# compute_module_Ethernet.net
KiCad netlist of a schematic drawn in Altium Designer
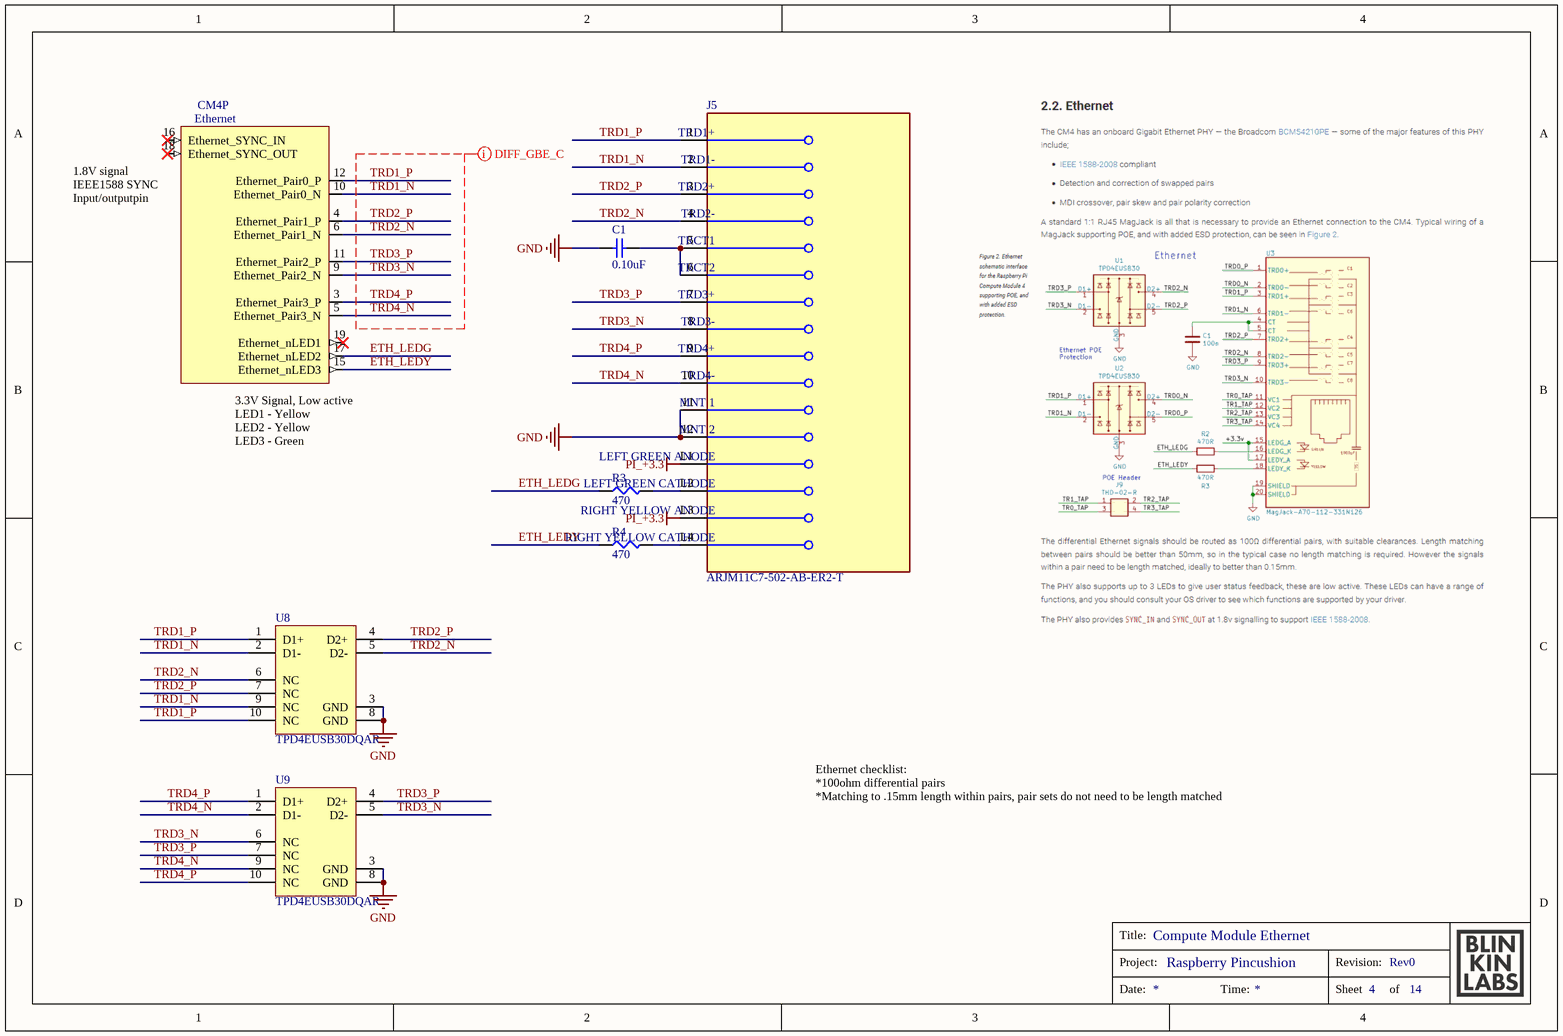
[diagram p0: compute module Ethernet.SchDoc]

(export (version "E")
  (design (tool "Eeschema 10.0.6"))
  (components
    (comp (ref "C1")
      (value "0.10uF")
      (footprint "CAPC1608X09L")
      (description "CAP CER 0.1UF 50V X7R 0603")
      (fields
        (field (name "PARTNUMBER") "GRM188R71H104KA93D")
        (field (name "DIGI-KEY PART NUMBER") "490-1519-1-ND")
      )
      (libsource (lib "cap_murata") (part "CAPACITOR"))
    )
    (comp (ref "CM4")
      (value "Raspberry Pi Compute Module 4")
      (footprint "CM4-F40C-100DS-0.4v_1.5mm_0mm")
      (description "Raspberry Pi Compute Module 4 by Amornthep Phunsin")
      (libsource (lib "CM4") (part "CM4"))
    )
    (comp (ref "J5")
      (value "ARJM11C7-502-AB-ER2-T")
      (footprint "FP-ARJM11C7-502-AB-ER2-T-MFG")
      (description "RJ45 JACK W/MAG 1X1 1000BASE-T")
      (fields
        (field (name "MANUFACTURER") "Abracon")
        (field (name "OCTOPART") "https://octopart.com/arjm11c7-502-ab-er2-t-abracon-86945316")
      )
      (libsource (lib "Altium Content Vault") (part "c9e9675df30893a1b3e4105448caa83"))
    )
    (comp (ref "R3")
      (value "470")
      (footprint "ERJ2G(0402)_L")
      (description "RES SMD 470 OHM 5% 1/10W 0402")
      (fields (field (name "PARTNUMBER") "ERJ-2GEJ471X") (field (name "DIGI-KEY PART NUMBER") "P470JCT-ND"))
      (libsource (lib "res_panasonic_erj_xls") (part "RESISTOR"))
    )
    (comp (ref "R4")
      (value "470")
      (footprint "ERJ2G(0402)_L")
      (description "RES SMD 470 OHM 5% 1/10W 0402")
      (fields (field (name "PARTNUMBER") "ERJ-2GEJ471X") (field (name "DIGI-KEY PART NUMBER") "P470JCT-ND"))
      (libsource (lib "res_panasonic_erj_xls") (part "RESISTOR"))
    )
    (comp (ref "U8")
      (value "TPD4EUSB30DQAR")
      (footprint "DQA0010A_V")
      (fields (field (name "MANUFACTURER") "Texas Instruments"))
      (libsource (lib "Altium Content Vault") (part "TI-TPD4EUSB30-SON_DQA-10"))
    )
    (comp (ref "U9")
      (value "TPD4EUSB30DQAR")
      (footprint "DQA0010A_V")
      (fields (field (name "MANUFACTURER") "Texas Instruments"))
      (libsource (lib "Altium Content Vault") (part "TI-TPD4EUSB30-SON_DQA-10"))
    )
  )
  (nets
    (net (code "1") (name "/ETH_LEDG") (class "Default")
      (node (ref "CM4") (pin "17") (pinfunction "Ethernet_nLED2_17") (pintype "output"))
      (node (ref "R3") (pin "1") (pinfunction "1_1") (pintype "passive"))
    )
    (net (code "2") (name "/ETH_LEDY") (class "Default")
      (node (ref "CM4") (pin "15") (pinfunction "Ethernet_nLED3_15") (pintype "output"))
      (node (ref "R4") (pin "1") (pinfunction "1_1") (pintype "passive"))
    )
    (net (code "3") (name "/TRD1_N") (class "Default")
      (node (ref "CM4") (pin "10") (pinfunction "Ethernet_Pair0_N_10") (pintype "passive"))
      (node (ref "J5") (pin "2") (pinfunction "TRD1-_2") (pintype "passive"))
      (node (ref "U8") (pin "2") (pinfunction "D1-_2") (pintype "passive"))
      (node (ref "U8") (pin "9") (pinfunction "NC_9") (pintype "passive"))
    )
    (net (code "4") (name "/TRD1_P") (class "Default")
      (node (ref "CM4") (pin "12") (pinfunction "Ethernet_Pair0_P_12") (pintype "passive"))
      (node (ref "J5") (pin "1") (pinfunction "TRD1+_1") (pintype "passive"))
      (node (ref "U8") (pin "1") (pinfunction "D1+_1") (pintype "passive"))
      (node (ref "U8") (pin "10") (pinfunction "NC_10") (pintype "passive"))
    )
    (net (code "5") (name "/TRD2_N") (class "Default")
      (node (ref "CM4") (pin "6") (pinfunction "Ethernet_Pair1_N_6") (pintype "passive"))
      (node (ref "J5") (pin "4") (pinfunction "TRD2-_4") (pintype "passive"))
      (node (ref "U8") (pin "5") (pinfunction "D2-_5") (pintype "passive"))
      (node (ref "U8") (pin "6") (pinfunction "NC_6") (pintype "passive"))
    )
    (net (code "6") (name "/TRD2_P") (class "Default")
      (node (ref "CM4") (pin "4") (pinfunction "Ethernet_Pair1_P_4") (pintype "passive"))
      (node (ref "J5") (pin "3") (pinfunction "TRD2+_3") (pintype "passive"))
      (node (ref "U8") (pin "4") (pinfunction "D2+_4") (pintype "passive"))
      (node (ref "U8") (pin "7") (pinfunction "NC_7") (pintype "passive"))
    )
    (net (code "7") (name "/TRD3_N") (class "Default")
      (node (ref "CM4") (pin "9") (pinfunction "Ethernet_Pair2_N_9") (pintype "passive"))
      (node (ref "J5") (pin "8") (pinfunction "TRD3-_8") (pintype "passive"))
      (node (ref "U9") (pin "5") (pinfunction "D2-_5") (pintype "passive"))
      (node (ref "U9") (pin "6") (pinfunction "NC_6") (pintype "passive"))
    )
    (net (code "8") (name "/TRD3_P") (class "Default")
      (node (ref "CM4") (pin "11") (pinfunction "Ethernet_Pair2_P_11") (pintype "passive"))
      (node (ref "J5") (pin "7") (pinfunction "TRD3+_7") (pintype "passive"))
      (node (ref "U9") (pin "4") (pinfunction "D2+_4") (pintype "passive"))
      (node (ref "U9") (pin "7") (pinfunction "NC_7") (pintype "passive"))
    )
    (net (code "9") (name "/TRD4_N") (class "Default")
      (node (ref "CM4") (pin "5") (pinfunction "Ethernet_Pair3_N_5") (pintype "passive"))
      (node (ref "J5") (pin "10") (pinfunction "TRD4-_10") (pintype "passive"))
      (node (ref "U9") (pin "2") (pinfunction "D1-_2") (pintype "passive"))
      (node (ref "U9") (pin "9") (pinfunction "NC_9") (pintype "passive"))
    )
    (net (code "10") (name "/TRD4_P") (class "Default")
      (node (ref "CM4") (pin "3") (pinfunction "Ethernet_Pair3_P_3") (pintype "passive"))
      (node (ref "J5") (pin "9") (pinfunction "TRD4+_9") (pintype "passive"))
      (node (ref "U9") (pin "1") (pinfunction "D1+_1") (pintype "passive"))
      (node (ref "U9") (pin "10") (pinfunction "NC_10") (pintype "passive"))
    )
    (net (code "11") (name "GND") (class "Default")
      (node (ref "C1") (pin "1") (pinfunction "1_1") (pintype "passive"))
      (node (ref "J5") (pin "11") (pinfunction "MNT_1_11") (pintype "passive"))
      (node (ref "J5") (pin "12") (pinfunction "MNT_2_12") (pintype "passive"))
      (node (ref "U8") (pin "3") (pinfunction "GND_3") (pintype "power_in"))
      (node (ref "U8") (pin "8") (pinfunction "GND_8") (pintype "power_in"))
      (node (ref "U9") (pin "3") (pinfunction "GND_3") (pintype "power_in"))
      (node (ref "U9") (pin "8") (pinfunction "GND_8") (pintype "power_in"))
    )
    (net (code "12") (name "Net-(J5-LEFT_GREEN_CATHODE)") (class "Default")
      (node (ref "J5") (pin "L2") (pinfunction "LEFT_GREEN_CATHODE_L2") (pintype "passive"))
      (node (ref "R3") (pin "2") (pinfunction "2_2") (pintype "passive"))
    )
    (net (code "13") (name "Net-(J5-RIGHT_YELLOW_CATHODE)") (class "Default")
      (node (ref "J5") (pin "L4") (pinfunction "RIGHT_YELLOW_CATHODE_L4") (pintype "passive"))
      (node (ref "R4") (pin "2") (pinfunction "2_2") (pintype "passive"))
    )
    (net (code "14") (name "Net-(J5-TRCT1)") (class "Default")
      (node (ref "C1") (pin "2") (pinfunction "2_2") (pintype "passive"))
      (node (ref "J5") (pin "5") (pinfunction "TRCT1_5") (pintype "passive"))
      (node (ref "J5") (pin "6") (pinfunction "TRCT2_6") (pintype "passive"))
    )
    (net (code "15") (name "PI_+3.3") (class "Default")
      (node (ref "J5") (pin "L1") (pinfunction "LEFT_GREEN_ANODE_L1") (pintype "passive"))
      (node (ref "J5") (pin "L3") (pinfunction "RIGHT_YELLOW_ANODE_L3") (pintype "passive"))
    )
    (net (code "16") (name "unconnected-(CM4P-Ethernet_SYNC_IN-Pad16)") (class "Default")
      (node (ref "CM4") (pin "16") (pinfunction "Ethernet_SYNC_IN_16") (pintype "input+no_connect"))
    )
    (net (code "17") (name "unconnected-(CM4P-Ethernet_SYNC_OUT-Pad18)") (class "Default")
      (node (ref "CM4") (pin "18") (pinfunction "Ethernet_SYNC_OUT_18") (pintype "input+no_connect"))
    )
    (net (code "18") (name "unconnected-(CM4P-Ethernet_nLED1-Pad19)") (class "Default")
      (node (ref "CM4") (pin "19") (pinfunction "Ethernet_nLED1_19") (pintype "output+no_connect"))
    )
  )
)
